# CurrentAmpl.net
KiCad netlist of a schematic drawn in Altium Designer
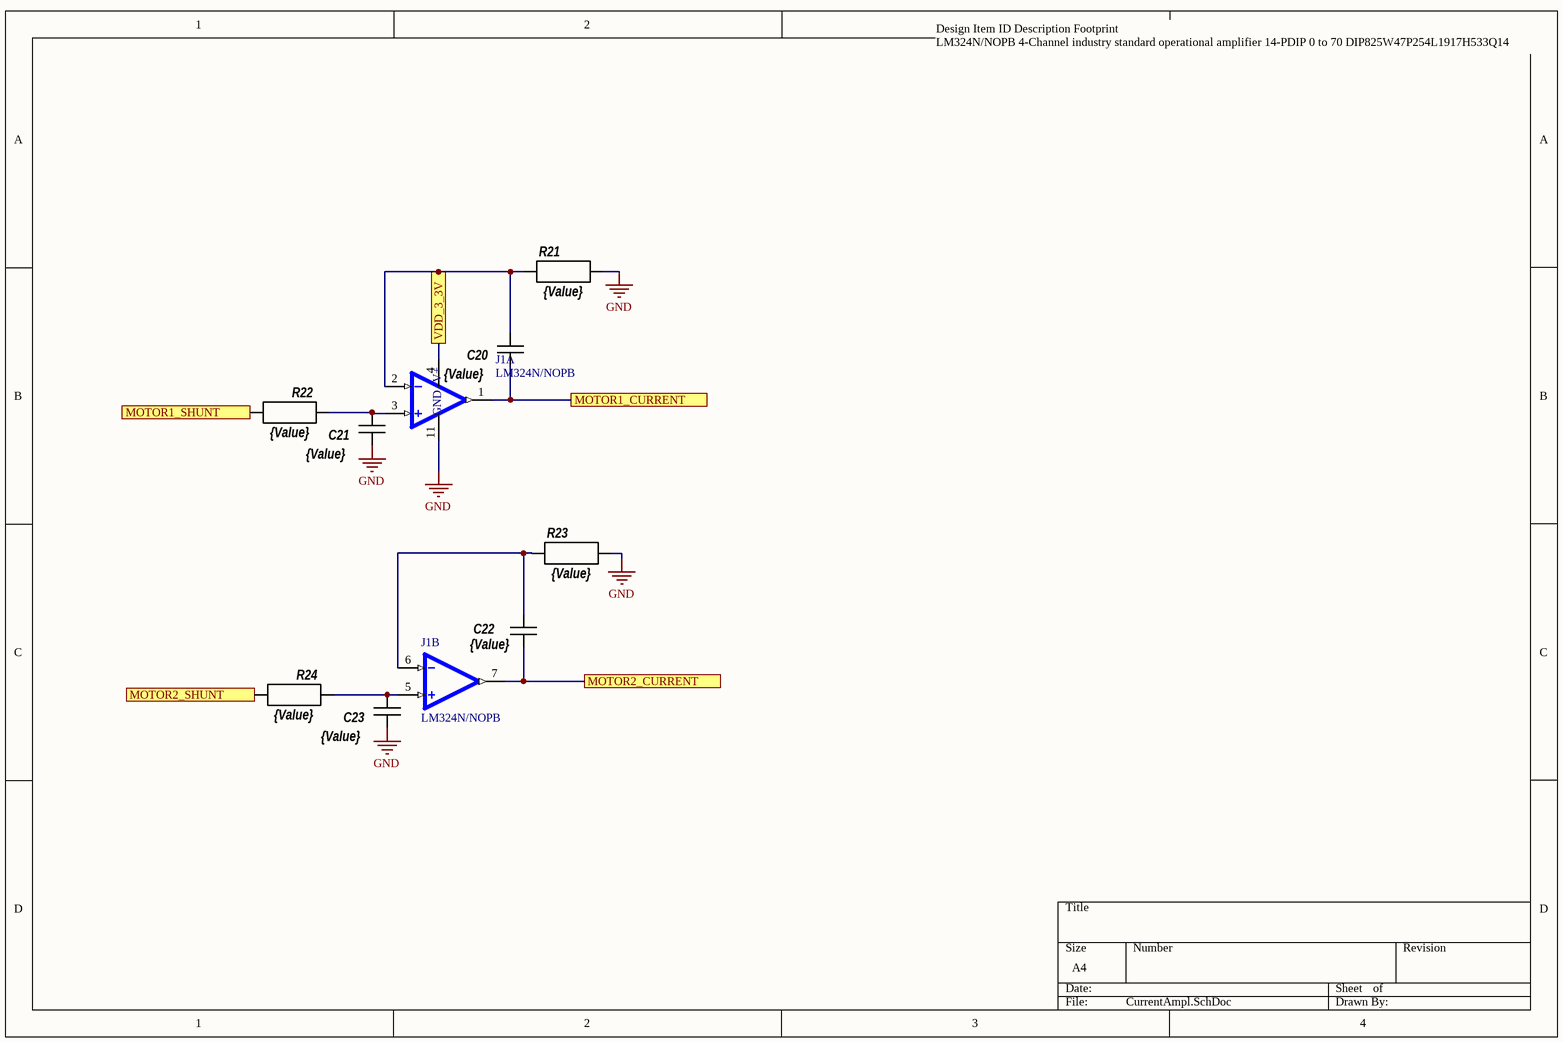
[diagram p0: CurrentAmpl.SchDoc]

(export (version "E")
  (design (tool "Eeschema 10.0.6"))
  (components
    (comp (ref "C20")
      (value "{Value}")
      (footprint "C0805")
      (description "Конденсатор 0805")
      (fields (field (name "MANUFACTURER") "Murata") (field (name "Comment") "Cap 0805"))
      (libsource (lib "GIS_SMD components") (part "Cap 0805"))
    )
    (comp (ref "C21")
      (value "{Value}")
      (footprint "C0805")
      (description "Конденсатор 0805")
      (fields (field (name "MANUFACTURER") "Murata") (field (name "Comment") "Cap 0805"))
      (libsource (lib "GIS_SMD components") (part "Cap 0805"))
    )
    (comp (ref "C22")
      (value "{Value}")
      (footprint "C0805")
      (description "Конденсатор 0805")
      (fields (field (name "MANUFACTURER") "Murata") (field (name "Comment") "Cap 0805"))
      (libsource (lib "GIS_SMD components") (part "Cap 0805"))
    )
    (comp (ref "C23")
      (value "{Value}")
      (footprint "C0805")
      (description "Конденсатор 0805")
      (fields (field (name "MANUFACTURER") "Murata") (field (name "Comment") "Cap 0805"))
      (libsource (lib "GIS_SMD components") (part "Cap 0805"))
    )
    (comp (ref "J1")
      (value "LM324N/NOPB")
      (footprint "DIP825W47P254L1917H533Q14")
      (description "4-Channel industry standard operational amplifier 14-PDIP 0 to 70")
      (fields (field (name "MP") "LM324N") (field (name "MF") "Texas Instruments"))
      (libsource (lib "LM324N_NOPB") (part "LM324N/NOPB"))
    )
    (comp (ref "R21")
      (value "{Value}")
      (footprint "R0805")
      (description "Резистор 0805")
      (fields (field (name "MANUFACTURER") "Yageo") (field (name "Comment") "Res 0805"))
      (libsource (lib "GIS_SMD components") (part "Res 0805"))
    )
    (comp (ref "R22")
      (value "{Value}")
      (footprint "R0805")
      (description "Резистор 0805")
      (fields (field (name "MANUFACTURER") "Yageo") (field (name "Comment") "Res 0805"))
      (libsource (lib "GIS_SMD components") (part "Res 0805"))
    )
    (comp (ref "R23")
      (value "{Value}")
      (footprint "R0805")
      (description "Резистор 0805")
      (fields (field (name "MANUFACTURER") "Yageo") (field (name "Comment") "Res 0805"))
      (libsource (lib "GIS_SMD components") (part "Res 0805"))
    )
    (comp (ref "R24")
      (value "{Value}")
      (footprint "R0805")
      (description "Резистор 0805")
      (fields (field (name "MANUFACTURER") "Yageo") (field (name "Comment") "Res 0805"))
      (libsource (lib "GIS_SMD components") (part "Res 0805"))
    )
  )
  (nets
    (net (code "1") (name "/MOTOR1_CURRENT") (class "Default")
      (node (ref "C20") (pin "2") (pinfunction "2_2") (pintype "passive"))
      (node (ref "J1") (pin "1") (pinfunction "1OUT_1") (pintype "output"))
    )
    (net (code "2") (name "/MOTOR1_SHUNT") (class "Default")
      (node (ref "R22") (pin "1") (pinfunction "1_1") (pintype "passive"))
    )
    (net (code "3") (name "/MOTOR2_CURRENT") (class "Default")
      (node (ref "C22") (pin "2") (pinfunction "2_2") (pintype "passive"))
      (node (ref "J1") (pin "7") (pinfunction "2OUT_7") (pintype "output"))
    )
    (net (code "4") (name "/MOTOR2_SHUNT") (class "Default")
      (node (ref "R24") (pin "1") (pinfunction "1_1") (pintype "passive"))
    )
    (net (code "5") (name "/VDD_3_3V") (class "Default")
      (node (ref "C20") (pin "1") (pinfunction "1_1") (pintype "passive"))
      (node (ref "J1") (pin "2") (pinfunction "1IN-_2") (pintype "input"))
      (node (ref "J1") (pin "4") (pinfunction "V+_4") (pintype "power_in"))
      (node (ref "R21") (pin "2") (pinfunction "2_2") (pintype "passive"))
    )
    (net (code "6") (name "GND") (class "Default")
      (node (ref "C21") (pin "2") (pinfunction "2_2") (pintype "passive"))
      (node (ref "C23") (pin "2") (pinfunction "2_2") (pintype "passive"))
      (node (ref "J1") (pin "11") (pinfunction "GND_11") (pintype "power_in"))
      (node (ref "R21") (pin "1") (pinfunction "1_1") (pintype "passive"))
      (node (ref "R23") (pin "1") (pinfunction "1_1") (pintype "passive"))
    )
    (net (code "7") (name "Net-(J1A-1IN+)") (class "Default")
      (node (ref "C21") (pin "1") (pinfunction "1_1") (pintype "passive"))
      (node (ref "J1") (pin "3") (pinfunction "1IN+_3") (pintype "input"))
      (node (ref "R22") (pin "2") (pinfunction "2_2") (pintype "passive"))
    )
    (net (code "8") (name "Net-(J1B-2IN+)") (class "Default")
      (node (ref "C23") (pin "1") (pinfunction "1_1") (pintype "passive"))
      (node (ref "J1") (pin "5") (pinfunction "2IN+_5") (pintype "input"))
      (node (ref "R24") (pin "2") (pinfunction "2_2") (pintype "passive"))
    )
    (net (code "9") (name "Net-(J1B-2IN-)") (class "Default")
      (node (ref "C22") (pin "1") (pinfunction "1_1") (pintype "passive"))
      (node (ref "J1") (pin "6") (pinfunction "2IN-_6") (pintype "input"))
      (node (ref "R23") (pin "2") (pinfunction "2_2") (pintype "passive"))
    )
  )
)
